# sensor.net
KiCad netlist of a schematic drawn in EAGLE
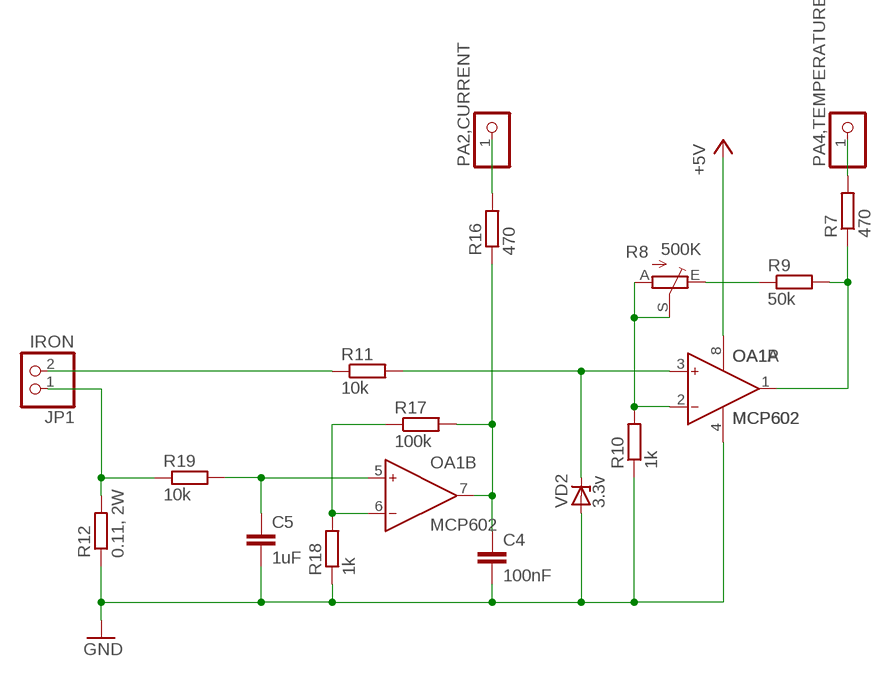
[diagram p0: schematic, sheet 1]

(export (version "E")
  (design (tool "Eeschema 10.0.6"))
  (components
    (comp (ref "C4")
      (value "100nF")
      (footprint "eagle-import:C025-024X044")
      (libsource (lib "eagle-import") (part "C-EU025-024X044"))
    )
    (comp (ref "C5")
      (value "1uF")
      (footprint "eagle-import:C025-024X044")
      (libsource (lib "eagle-import") (part "C-EU025-024X044"))
    )
    (comp (ref "JP1")
      (value "IRON")
      (footprint "eagle-import:1X02")
      (libsource (lib "eagle-import") (part "PINHD-1X2"))
    )
    (comp (ref "OA1")
      (value "MCP602")
      (footprint "eagle-import:DIL08")
      (libsource (lib "eagle-import") (part "AD822N"))
    )
    (comp (ref "PA2,CURRENT")
      (value "PINHD-1X1")
      (footprint "eagle-import:1X01")
      (libsource (lib "eagle-import") (part "PINHD-1X1"))
    )
    (comp (ref "PA4,TEMPERATURE")
      (value "PINHD-1X1")
      (footprint "eagle-import:1X01")
      (libsource (lib "eagle-import") (part "PINHD-1X1"))
    )
    (comp (ref "R7")
      (value "470")
      (footprint "eagle-import:0204_5")
      (libsource (lib "eagle-import") (part "R-EU_0204/5"))
    )
    (comp (ref "R8")
      (value "500K")
      (footprint "eagle-import:B64Y")
      (libsource (lib "eagle-import") (part "TRIM_EU-B64Y"))
    )
    (comp (ref "R9")
      (value "50k")
      (footprint "eagle-import:0204_5")
      (libsource (lib "eagle-import") (part "R-EU_0204/5"))
    )
    (comp (ref "R10")
      (value "1k")
      (footprint "eagle-import:0204_5")
      (libsource (lib "eagle-import") (part "R-EU_0204/5"))
    )
    (comp (ref "R11")
      (value "10k")
      (footprint "eagle-import:0204_5")
      (libsource (lib "eagle-import") (part "R-EU_0204/5"))
    )
    (comp (ref "R12")
      (value "0.11, 2W")
      (footprint "eagle-import:0204_5")
      (libsource (lib "eagle-import") (part "R-EU_0204/5"))
    )
    (comp (ref "R16")
      (value "470")
      (footprint "eagle-import:0204_5")
      (libsource (lib "eagle-import") (part "R-EU_0204/5"))
    )
    (comp (ref "R17")
      (value "100k")
      (footprint "eagle-import:0204_5")
      (libsource (lib "eagle-import") (part "R-EU_0204/5"))
    )
    (comp (ref "R18")
      (value "1k")
      (footprint "eagle-import:0204_5")
      (libsource (lib "eagle-import") (part "R-EU_0204/5"))
    )
    (comp (ref "R19")
      (value "10k")
      (footprint "eagle-import:0204_5")
      (libsource (lib "eagle-import") (part "R-EU_0204/5"))
    )
    (comp (ref "VD2")
      (value "3.3v")
      (footprint "eagle-import:C1702-15")
      (libsource (lib "eagle-import") (part "ZENER-DIODEC1702-15"))
    )
  )
  (nets
    (net (code "1") (name "+5V") (class "Default")
      (node (ref "OA1") (pin "8") (pinfunction "V+_8") (pintype "power_in"))
    )
    (net (code "2") (name "GND") (class "Default")
      (node (ref "C4") (pin "2") (pinfunction "2_2") (pintype "passive"))
      (node (ref "C5") (pin "2") (pinfunction "2_2") (pintype "passive"))
      (node (ref "OA1") (pin "4") (pinfunction "V-_4") (pintype "power_in"))
      (node (ref "R10") (pin "1") (pinfunction "1_1") (pintype "passive"))
      (node (ref "R12") (pin "1") (pinfunction "1_1") (pintype "passive"))
      (node (ref "R18") (pin "1") (pinfunction "1_1") (pintype "passive"))
      (node (ref "VD2") (pin "A") (pinfunction "A_A") (pintype "passive"))
    )
    (net (code "3") (name "Net-(JP1-Pad1)") (class "Default")
      (node (ref "JP1") (pin "1") (pinfunction "1_1") (pintype "passive"))
      (node (ref "R12") (pin "2") (pinfunction "2_2") (pintype "passive"))
      (node (ref "R19") (pin "1") (pinfunction "1_1") (pintype "passive"))
    )
    (net (code "4") (name "Net-(JP1-Pad2)") (class "Default")
      (node (ref "JP1") (pin "2") (pinfunction "2_2") (pintype "passive"))
      (node (ref "R11") (pin "1") (pinfunction "1_1") (pintype "passive"))
    )
    (net (code "5") (name "Net-(OA1A-IN+)") (class "Default")
      (node (ref "OA1") (pin "3") (pinfunction "IN+_3") (pintype "input"))
      (node (ref "R11") (pin "2") (pinfunction "2_2") (pintype "passive"))
      (node (ref "VD2") (pin "C") (pinfunction "C_C") (pintype "passive"))
    )
    (net (code "6") (name "Net-(OA1A-IN-)") (class "Default")
      (node (ref "OA1") (pin "2") (pinfunction "IN-_2") (pintype "input"))
      (node (ref "R10") (pin "2") (pinfunction "2_2") (pintype "passive"))
      (node (ref "R8") (pin "A") (pinfunction "A_A") (pintype "passive"))
      (node (ref "R8") (pin "S") (pinfunction "S_S") (pintype "passive"))
    )
    (net (code "7") (name "Net-(OA1A-OUT)") (class "Default")
      (node (ref "OA1") (pin "1") (pinfunction "OUT_1") (pintype "output"))
      (node (ref "R7") (pin "1") (pinfunction "1_1") (pintype "passive"))
      (node (ref "R9") (pin "2") (pinfunction "2_2") (pintype "passive"))
    )
    (net (code "8") (name "Net-(OA1B-IN+)") (class "Default")
      (node (ref "C5") (pin "1") (pinfunction "1_1") (pintype "passive"))
      (node (ref "OA1") (pin "5") (pinfunction "IN+_5") (pintype "input"))
      (node (ref "R19") (pin "2") (pinfunction "2_2") (pintype "passive"))
    )
    (net (code "9") (name "Net-(OA1B-IN-)") (class "Default")
      (node (ref "OA1") (pin "6") (pinfunction "IN-_6") (pintype "input"))
      (node (ref "R17") (pin "1") (pinfunction "1_1") (pintype "passive"))
      (node (ref "R18") (pin "2") (pinfunction "2_2") (pintype "passive"))
    )
    (net (code "10") (name "Net-(OA1B-OUT)") (class "Default")
      (node (ref "C4") (pin "1") (pinfunction "1_1") (pintype "passive"))
      (node (ref "OA1") (pin "7") (pinfunction "OUT_7") (pintype "output"))
      (node (ref "R16") (pin "1") (pinfunction "1_1") (pintype "passive"))
      (node (ref "R17") (pin "2") (pinfunction "2_2") (pintype "passive"))
    )
    (net (code "11") (name "Net-(PA2,CURRENT-Pad1)") (class "Default")
      (node (ref "PA2,CURRENT") (pin "1") (pinfunction "1_1") (pintype "passive"))
      (node (ref "R16") (pin "2") (pinfunction "2_2") (pintype "passive"))
    )
    (net (code "12") (name "Net-(PA4,TEMPERATURE-Pad1)") (class "Default")
      (node (ref "PA4,TEMPERATURE") (pin "1") (pinfunction "1_1") (pintype "passive"))
      (node (ref "R7") (pin "2") (pinfunction "2_2") (pintype "passive"))
    )
    (net (code "13") (name "Net-(R8-PadE)") (class "Default")
      (node (ref "R8") (pin "E") (pinfunction "E_E") (pintype "passive"))
      (node (ref "R9") (pin "1") (pinfunction "1_1") (pintype "passive"))
    )
  )
)
